# usb_Serial_module_ch340g.net
KiCad netlist of a schematic drawn in EAGLE
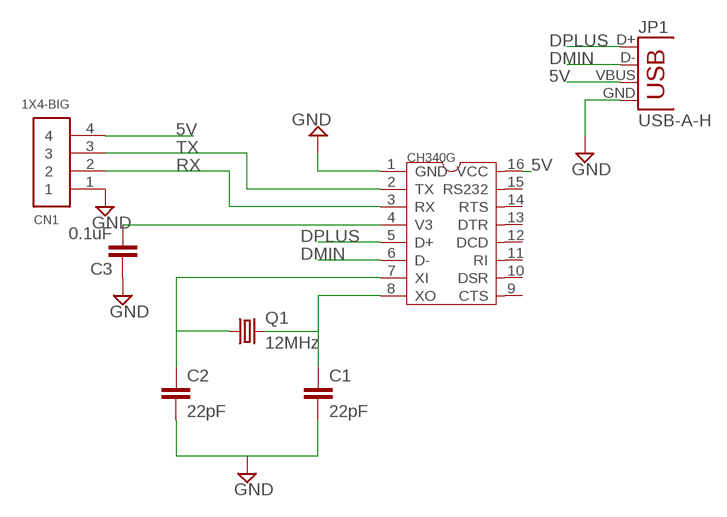
[diagram p0: schematic, sheet 1]

(export (version "E")
  (design (tool "Eeschema 10.0.6"))
  (components
    (comp (ref "C1")
      (value "22pF")
      (footprint "eagle-import:0603-CAP")
      (libsource (lib "eagle-import") (part "CAP0603-CAP"))
    )
    (comp (ref "C2")
      (value "22pF")
      (footprint "eagle-import:0603-CAP")
      (libsource (lib "eagle-import") (part "CAP0603-CAP"))
    )
    (comp (ref "C3")
      (value "0.1uF")
      (footprint "eagle-import:0603-CAP")
      (libsource (lib "eagle-import") (part "CAP0603-CAP"))
    )
    (comp (ref "CH340G")
      (value "CH340GCH340G")
      (footprint "eagle-import:SOP-16")
      (libsource (lib "eagle-import") (part "CH340GCH340G"))
    )
    (comp (ref "CN1")
      (value "1X4-BIG")
      (footprint "eagle-import:1X04-BIG")
      (libsource (lib "eagle-import") (part "1X4-BIG"))
    )
    (comp (ref "JP1")
      (value "USB-A-H")
      (footprint "eagle-import:USB-A-H")
      (libsource (lib "eagle-import") (part "USB-A-H"))
    )
    (comp (ref "Q1")
      (value "12MHz")
      (footprint "eagle-import:HC49U70")
      (libsource (lib "eagle-import") (part "CRYSTALHC49U70"))
    )
  )
  (nets
    (net (code "1") (name "/5V") (class "Default")
      (node (ref "CH340G") (pin "16") (pinfunction "VCC_16") (pintype "output"))
      (node (ref "CN1") (pin "4") (pinfunction "4_4") (pintype "bidirectional"))
      (node (ref "JP1") (pin "VBUS") (pinfunction "VBUS_VBUS") (pintype "bidirectional"))
    )
    (net (code "2") (name "/DMIN") (class "Default")
      (node (ref "CH340G") (pin "6") (pinfunction "D-_6") (pintype "bidirectional"))
      (node (ref "JP1") (pin "D-") (pinfunction "D-_D-") (pintype "bidirectional"))
    )
    (net (code "3") (name "/DPLUS") (class "Default")
      (node (ref "CH340G") (pin "5") (pinfunction "D+_5") (pintype "bidirectional"))
      (node (ref "JP1") (pin "D+") (pinfunction "D+_D+") (pintype "bidirectional"))
    )
    (net (code "4") (name "/RI") (class "Default")
      (node (ref "CH340G") (pin "11") (pinfunction "RI_11") (pintype "power_in"))
    )
    (net (code "5") (name "/RX") (class "Default")
      (node (ref "CH340G") (pin "3") (pinfunction "RX_3") (pintype "bidirectional"))
      (node (ref "CN1") (pin "2") (pinfunction "2_2") (pintype "bidirectional"))
    )
    (net (code "6") (name "/TX") (class "Default")
      (node (ref "CH340G") (pin "2") (pinfunction "TX_2") (pintype "bidirectional"))
      (node (ref "CN1") (pin "3") (pinfunction "3_3") (pintype "bidirectional"))
    )
    (net (code "7") (name "GND") (class "Default")
      (node (ref "C1") (pin "2") (pinfunction "2_2") (pintype "passive"))
      (node (ref "C2") (pin "2") (pinfunction "2_2") (pintype "passive"))
      (node (ref "C3") (pin "1") (pinfunction "1_1") (pintype "passive"))
      (node (ref "CH340G") (pin "1") (pinfunction "GND_1") (pintype "bidirectional"))
      (node (ref "CN1") (pin "1") (pinfunction "1_1") (pintype "bidirectional"))
      (node (ref "JP1") (pin "GND") (pinfunction "GND_GND") (pintype "bidirectional"))
    )
    (net (code "8") (name "Net-(CH340G-V3)") (class "Default")
      (node (ref "C3") (pin "2") (pinfunction "2_2") (pintype "passive"))
      (node (ref "CH340G") (pin "4") (pinfunction "V3_4") (pintype "bidirectional"))
    )
    (net (code "9") (name "Net-(CH340G-XI)") (class "Default")
      (node (ref "C2") (pin "1") (pinfunction "1_1") (pintype "passive"))
      (node (ref "CH340G") (pin "7") (pinfunction "XI_7") (pintype "power_in"))
      (node (ref "Q1") (pin "1") (pinfunction "1_1") (pintype "passive"))
    )
    (net (code "10") (name "Net-(CH340G-XO)") (class "Default")
      (node (ref "C1") (pin "1") (pinfunction "1_1") (pintype "passive"))
      (node (ref "CH340G") (pin "8") (pinfunction "XO_8") (pintype "input"))
      (node (ref "Q1") (pin "2") (pinfunction "2_2") (pintype "passive"))
    )
    (net (code "11") (name "unconnected-(CH340G-CTS-Pad9)") (class "Default")
      (node (ref "CH340G") (pin "9") (pinfunction "CTS_9") (pintype "bidirectional"))
    )
    (net (code "12") (name "unconnected-(CH340G-DCD-Pad12)") (class "Default")
      (node (ref "CH340G") (pin "12") (pinfunction "DCD_12") (pintype "output"))
    )
    (net (code "13") (name "unconnected-(CH340G-DSR-Pad10)") (class "Default")
      (node (ref "CH340G") (pin "10") (pinfunction "DSR_10") (pintype "bidirectional"))
    )
    (net (code "14") (name "unconnected-(CH340G-DTR-Pad13)") (class "Default")
      (node (ref "CH340G") (pin "13") (pinfunction "DTR_13") (pintype "input"))
    )
    (net (code "15") (name "unconnected-(CH340G-RS232-Pad15)") (class "Default")
      (node (ref "CH340G") (pin "15") (pinfunction "RS232_15") (pintype "input"))
    )
    (net (code "16") (name "unconnected-(CH340G-RTS-Pad14)") (class "Default")
      (node (ref "CH340G") (pin "14") (pinfunction "RTS_14") (pintype "input"))
    )
  )
)
